# 03_PWR.net
KiCad netlist of a schematic drawn in Altium Designer
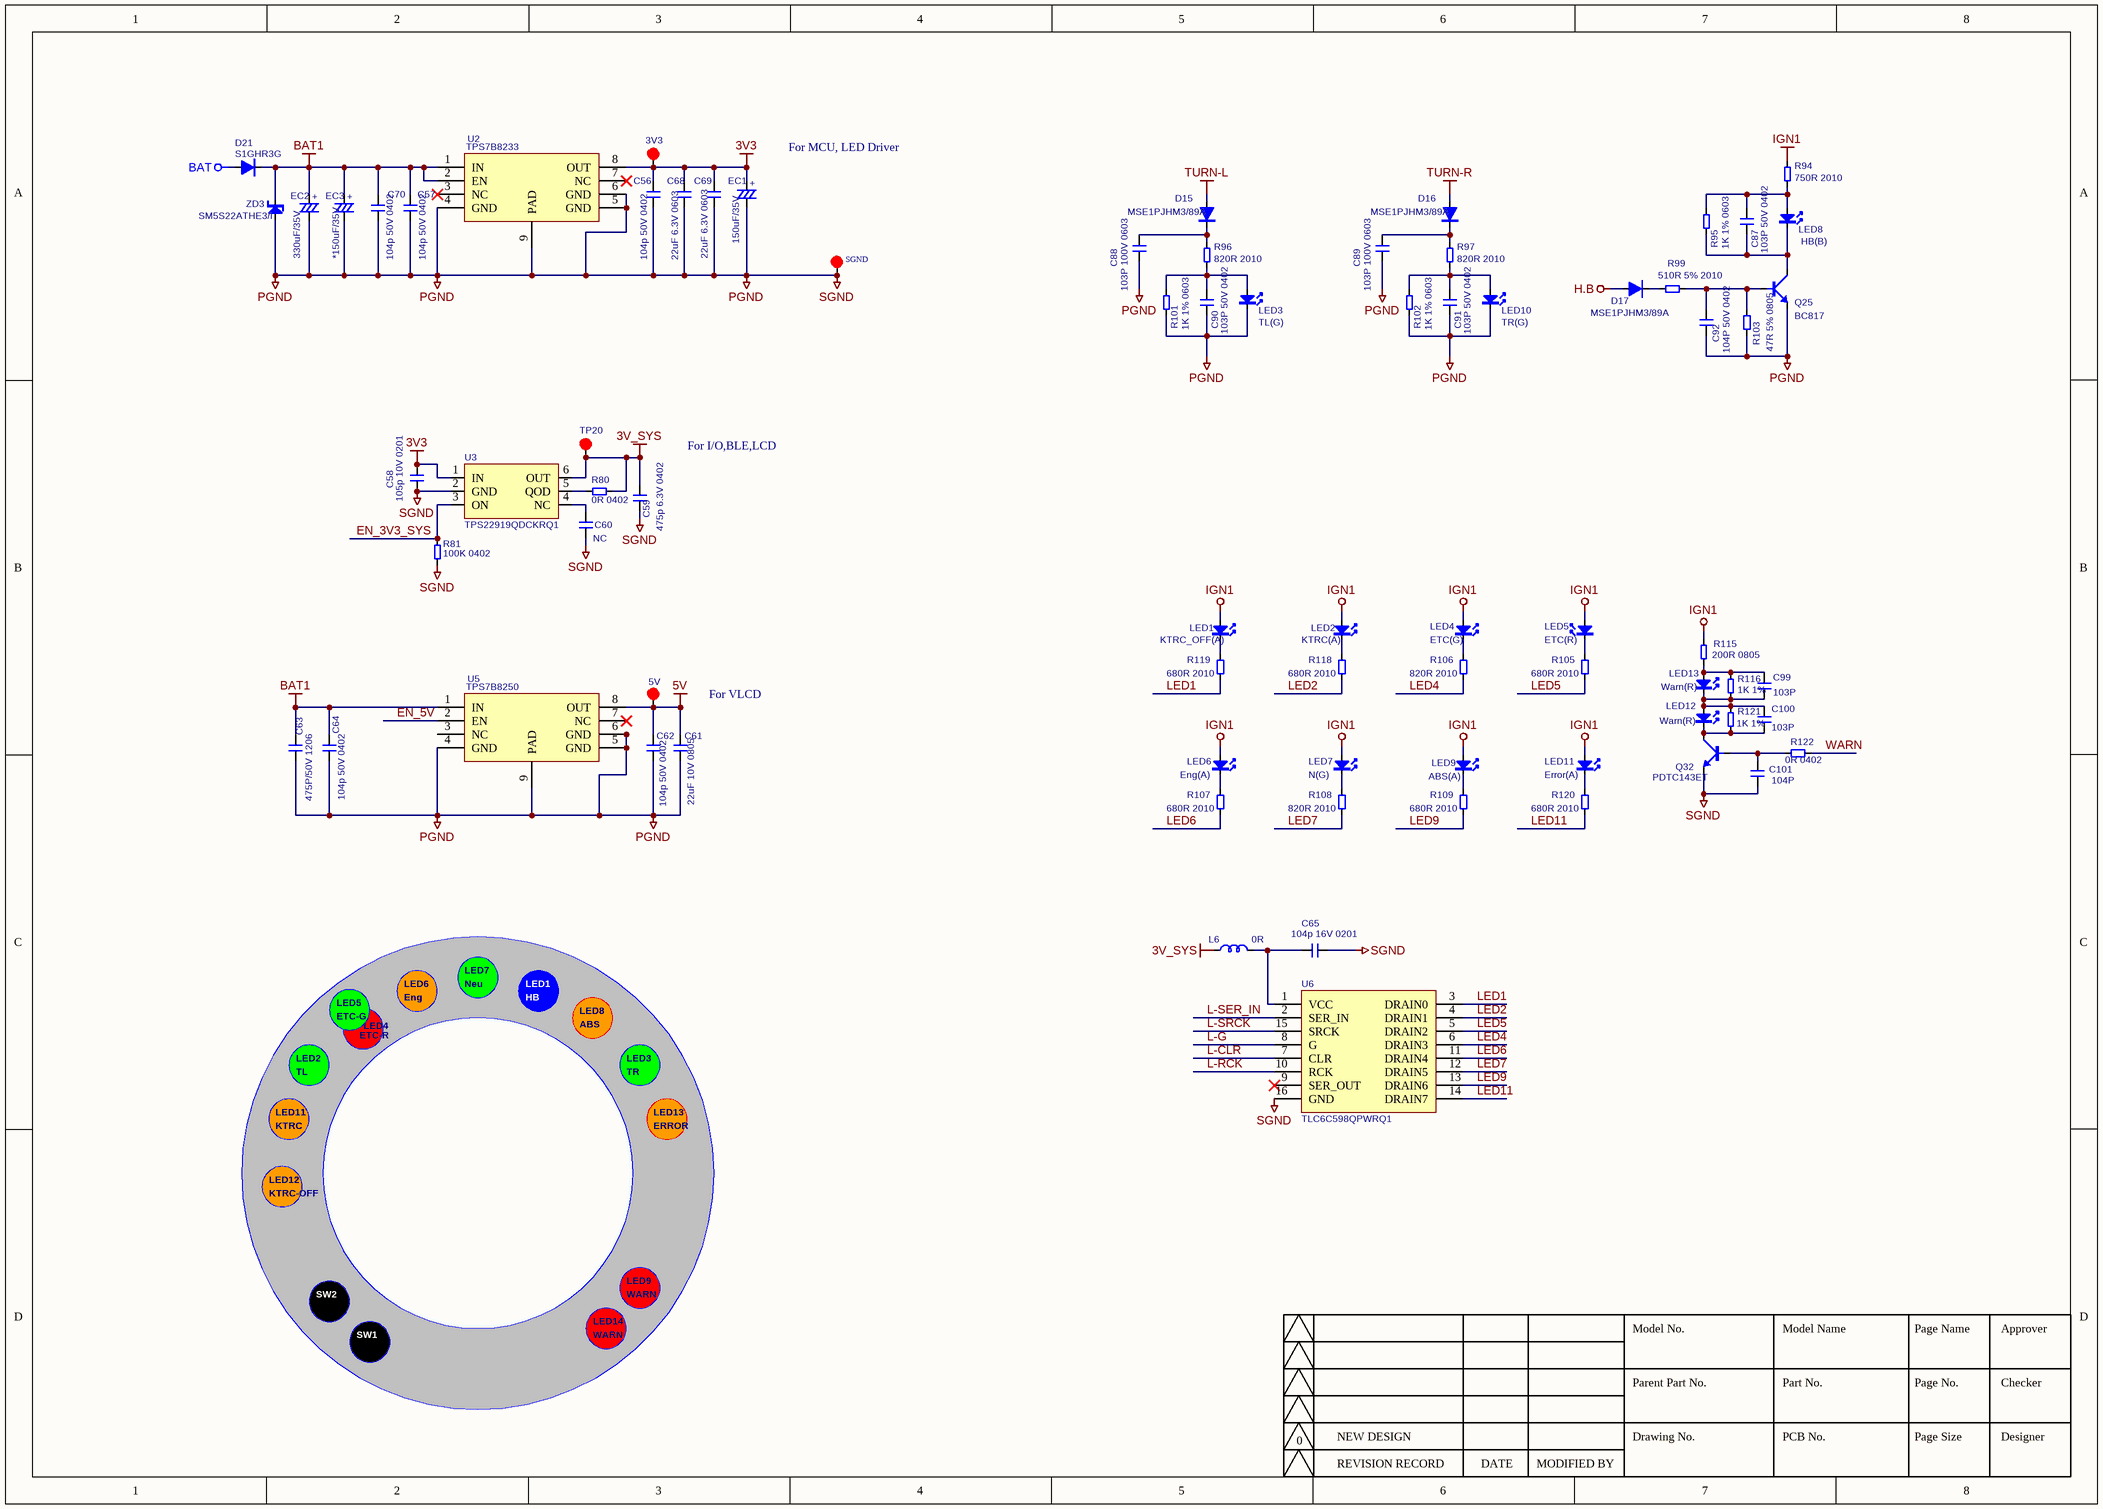
[diagram p0: 03_PWR.SchDoc]

(export (version "E")
  (design (tool "Eeschema 10.0.6"))
  (components
    (comp (ref "3V3") (value "TEST") (footprint "TEST") (libsource (lib "CTE-Lib(Meter)") (part "TEST")))
    (comp (ref "5V") (value "TEST") (footprint "TEST") (libsource (lib "CTE-Lib(Meter)") (part "TEST")))
    (comp (ref "C56")
      (value "104p 50V 0402")
      (footprint "C0402")
      (description "Capacitor")
      (libsource (lib "*") (part "C"))
    )
    (comp (ref "C57")
      (value "104p 50V 0402")
      (footprint "C0402")
      (description "Capacitor")
      (libsource (lib "*") (part "C"))
    )
    (comp (ref "C58")
      (value "105p 10V 0201")
      (footprint "C0201")
      (description "Capacitor")
      (libsource (lib "*") (part "C"))
    )
    (comp (ref "C59")
      (value "475p 6.3V 0402")
      (footprint "C0402")
      (description "4.7uF 6.3V 0402")
      (fields (field (name "VOLTAGE") "6.3V"))
      (libsource (lib "CTE") (part "C"))
    )
    (comp (ref "C60")
      (value "NC")
      (footprint "C0402")
      (description "Capacitor")
      (libsource (lib "CTE") (part "C"))
    )
    (comp (ref "C61")
      (value "22uF 10V 0805")
      (footprint "C0805")
      (description "Capacitor")
      (libsource (lib "CTE") (part "C"))
    )
    (comp (ref "C62")
      (value "104p 50V 0402")
      (footprint "C0402")
      (description "Capacitor")
      (libsource (lib "*") (part "C"))
    )
    (comp (ref "C63")
      (value "475P/50V 1206")
      (footprint "C1206")
      (description "Capacitor")
      (libsource (lib "CTE") (part "C"))
    )
    (comp (ref "C64")
      (value "104p 50V 0402")
      (footprint "C0402")
      (description "Capacitor")
      (libsource (lib "*") (part "C"))
    )
    (comp (ref "C65")
      (value "104p 16V 0201")
      (footprint "C0201")
      (description "Capacitor")
      (libsource (lib "*") (part "C"))
    )
    (comp (ref "C68")
      (value "22uF 6.3V 0603")
      (footprint "C0603")
      (description "Capacitor")
      (libsource (lib "CTE") (part "C"))
    )
    (comp (ref "C69")
      (value "22uF 6.3V 0603")
      (footprint "C0603")
      (description "Capacitor")
      (libsource (lib "CTE") (part "C"))
    )
    (comp (ref "C70")
      (value "104p 50V 0402")
      (footprint "C0402")
      (description "Capacitor")
      (libsource (lib "*") (part "C"))
    )
    (comp (ref "C87")
      (value "103P 50V 0402")
      (footprint "C0402")
      (description "Capacitor")
      (libsource (lib "CTE") (part "C"))
    )
    (comp (ref "C88")
      (value "103P 100V 0603")
      (footprint "C0603")
      (description "Capacitor")
      (libsource (lib "CTE") (part "C"))
    )
    (comp (ref "C89")
      (value "103P 100V 0603")
      (footprint "C0603")
      (description "Capacitor")
      (libsource (lib "CTE") (part "C"))
    )
    (comp (ref "C90")
      (value "103P 50V 0402")
      (footprint "C0402")
      (description "Capacitor")
      (libsource (lib "CTE") (part "C"))
    )
    (comp (ref "C91")
      (value "103P 50V 0402")
      (footprint "C0402")
      (description "Capacitor")
      (libsource (lib "CTE") (part "C"))
    )
    (comp (ref "C92")
      (value "104P 50V 0402")
      (footprint "C0402")
      (description "Capacitor")
      (libsource (lib "CTE") (part "C"))
    )
    (comp (ref "C99")
      (value "103P")
      (footprint "C0402")
      (description "Capacitor")
      (libsource (lib "CTE") (part "C"))
    )
    (comp (ref "C100")
      (value "103P")
      (footprint "C0402")
      (description "Capacitor")
      (libsource (lib "CTE") (part "C"))
    )
    (comp (ref "C101")
      (value "104P")
      (footprint "C0402")
      (description "Capacitor")
      (libsource (lib "CTE") (part "C"))
    )
    (comp (ref "D15")
      (value "MSE1PJHM3/89A")
      (footprint "D-DO-219AD")
      (description "SK54-AU/BAS16/RR264/1N4148/FM4004/SS14/SSL14/V15PL50/DO-219AD")
      (libsource (lib "") (part "D-SMD_1"))
    )
    (comp (ref "D16")
      (value "MSE1PJHM3/89A")
      (footprint "D-DO-219AD")
      (description "SK54-AU/BAS16/RR264/1N4148/FM4004/SS14/SSL14/V15PL50/DO-219AD")
      (libsource (lib "") (part "D-SMD_1"))
    )
    (comp (ref "D17")
      (value "MSE1PJHM3/89A")
      (footprint "D-DO-219AD")
      (description "SK54-AU/BAS16/RR264/1N4148/FM4004/SS14/SSL14/V15PL50/DO-219AD")
      (libsource (lib "CTE") (part "D-SMD"))
    )
    (comp (ref "D21")
      (value "S1GHR3G")
      (footprint "D-SMA")
      (description "BAS16/RR264/1N4148/FM4004/SS14/SSL14/V15PL50")
      (libsource (lib "CTE") (part "D-SMD"))
    )
    (comp (ref "EC1")
      (value "150uF/35V")
      (footprint "EC-[6.8*8]")
      (description "電解電容")
      (libsource (lib "CTE") (part "C-EC"))
    )
    (comp (ref "EC2")
      (value "330uF/35V")
      (footprint "EC-[8.5*10]")
      (description "電解電容")
      (libsource (lib "CTE") (part "C-EC"))
    )
    (comp (ref "EC3")
      (value "*150uF/35V")
      (footprint "EC-[6.8*8]")
      (description "電解電容")
      (libsource (lib "CTE") (part "C-EC"))
    )
    (comp (ref "L6")
      (value "0R")
      (footprint "0603")
      (description "BEAD101")
      (libsource (lib "CTE") (part "L"))
    )
    (comp (ref "LED1") (value "KTRC_OFF(A)") (footprint "LED-1206") (libsource (lib "CTE") (part "LED")))
    (comp (ref "LED2") (value "KTRC(A)") (footprint "LED-1206") (libsource (lib "CTE") (part "LED")))
    (comp (ref "LED3") (value "TL(G)") (footprint "LED-1206") (libsource (lib "CTE") (part "LED")))
    (comp (ref "LED4") (value "ETC(G)") (footprint "LED-1206") (libsource (lib "CTE") (part "LED")))
    (comp (ref "LED5") (value "ETC(R)") (footprint "LED-1206") (libsource (lib "") (part "LED_1")))
    (comp (ref "LED6") (value "Eng(A)") (footprint "LED-1206") (libsource (lib "CTE") (part "LED")))
    (comp (ref "LED7") (value "N(G)") (footprint "LED-1206") (libsource (lib "CTE") (part "LED")))
    (comp (ref "LED8") (value "HB(B)") (footprint "LED-1206") (libsource (lib "CTE") (part "LED")))
    (comp (ref "LED9") (value "ABS(A)") (footprint "LED-1206") (libsource (lib "CTE") (part "LED")))
    (comp (ref "LED10") (value "TR(G)") (footprint "LED-1206") (libsource (lib "CTE") (part "LED")))
    (comp (ref "LED11") (value "Error(A)") (footprint "LED-1206") (libsource (lib "CTE") (part "LED")))
    (comp (ref "LED12") (value "Warn(R)") (footprint "LED-1206") (libsource (lib "CTE") (part "LED")))
    (comp (ref "LED13") (value "Warn(R)") (footprint "LED-1206") (libsource (lib "CTE") (part "LED")))
    (comp (ref "Q25")
      (value "BC817")
      (footprint "SOT23-RF")
      (description "BC817，PDTC143ET，2SD2211，2SD1918")
      (libsource (lib "") (part "Q-NPN(BCE)_1"))
    )
    (comp (ref "Q32")
      (value "PDTC143ET")
      (footprint "SOT23-RF")
      (description "BC817/PDTC143ET/2SD2211/2SD1918")
      (libsource (lib "CTE") (part "Q-NPN(BCE)"))
    )
    (comp (ref "R80")
      (value "0R 0402")
      (footprint "0402")
      (description "0603")
      (libsource (lib "CTE") (part "R-0603"))
    )
    (comp (ref "R81") (value "100K 0402") (footprint "0402") (libsource (lib "*") (part "R")))
    (comp (ref "R94") (value "750R 2010") (footprint "2010") (libsource (lib "*") (part "R")))
    (comp (ref "R95") (value "1K 1% 0603") (footprint "0603") (libsource (lib "*") (part "R")))
    (comp (ref "R96") (value "820R 2010") (footprint "2010") (libsource (lib "*") (part "R")))
    (comp (ref "R97") (value "820R 2010") (footprint "2010") (libsource (lib "*") (part "R")))
    (comp (ref "R99") (value "510R 5% 2010") (footprint "2010") (libsource (lib "CTE") (part "R")))
    (comp (ref "R101") (value "1K 1% 0603") (footprint "0603") (libsource (lib "*") (part "R")))
    (comp (ref "R102") (value "1K 1% 0603") (footprint "0603") (libsource (lib "*") (part "R")))
    (comp (ref "R103") (value "47R 5% 0805") (footprint "0805") (libsource (lib "CTE") (part "R")))
    (comp (ref "R105")
      (value "680R 2010")
      (footprint "2010")
      (description "2010")
      (libsource (lib "CTE") (part "R-2010"))
    )
    (comp (ref "R106")
      (value "820R 2010")
      (footprint "2010")
      (description "2010")
      (libsource (lib "CTE") (part "R-2010"))
    )
    (comp (ref "R107")
      (value "680R 2010")
      (footprint "2010")
      (description "2010")
      (libsource (lib "CTE") (part "R-2010"))
    )
    (comp (ref "R108")
      (value "820R 2010")
      (footprint "2010")
      (description "2010")
      (libsource (lib "CTE") (part "R-2010"))
    )
    (comp (ref "R109")
      (value "680R 2010")
      (footprint "2010")
      (description "2010")
      (libsource (lib "CTE") (part "R-2010"))
    )
    (comp (ref "R115") (value "200R 0805") (footprint "0805") (libsource (lib "*") (part "R")))
    (comp (ref "R116") (value "1K 1%") (footprint "0603") (libsource (lib "*") (part "R")))
    (comp (ref "R118")
      (value "680R 2010")
      (footprint "2010")
      (description "2010")
      (libsource (lib "CTE") (part "R-2010"))
    )
    (comp (ref "R119")
      (value "680R 2010")
      (footprint "2010")
      (description "2010")
      (libsource (lib "CTE") (part "R-2010"))
    )
    (comp (ref "R120")
      (value "680R 2010")
      (footprint "2010")
      (description "2010")
      (libsource (lib "CTE") (part "R-2010"))
    )
    (comp (ref "R121") (value "1K 1%") (footprint "0603") (libsource (lib "*") (part "R")))
    (comp (ref "R122") (value "0R 0402") (footprint "0402") (libsource (lib "CTE") (part "R")))
    (comp (ref "SGND") (value "TEST") (footprint "TEST") (libsource (lib "CTE") (part "TEST")))
    (comp (ref "TP20") (value "TEST") (footprint "TEST") (libsource (lib "CTE") (part "TEST")))
    (comp (ref "U2")
      (value "TPS7B8233")
      (footprint "IC-MSOP8(3*3mm)")
      (libsource (lib "CTE") (part "IC-TPS7B82-Q1"))
    )
    (comp (ref "U3")
      (value "TPS22919QDCKRQ1")
      (footprint "IC-R-PDSO-G6")
      (libsource (lib "Schlib1") (part "TPS22919QDCKRQ1"))
    )
    (comp (ref "U5")
      (value "TPS7B8250")
      (footprint "IC-MSOP8(3*3mm)")
      (libsource (lib "CTE") (part "IC-TPS7B82-Q1"))
    )
    (comp (ref "U6")
      (value "TLC6C598QPWRQ1")
      (footprint "IC-TSSOP16")
      (libsource (lib "TFT_Test Card-00") (part "IC-TLC6C598"))
    )
    (comp (ref "ZD3") (value "SM5S22ATHE3/I") (footprint "ZD-DO218AB") (libsource (lib "CTE") (part "ZENER")))
  )
  (nets
    (net (code "1") (name "/EN_3V3_SYS") (class "Default")
      (node (ref "R81") (pin "1") (pinfunction "1_1") (pintype "passive"))
      (node (ref "U3") (pin "3") (pinfunction "ON_3") (pintype "passive"))
    )
    (net (code "2") (name "/EN_5V") (class "Default")
      (node (ref "U5") (pin "2") (pinfunction "EN_2") (pintype "passive"))
    )
    (net (code "3") (name "/L-CLR") (class "Default")
      (node (ref "U6") (pin "7") (pinfunction "CLR_7") (pintype "passive"))
    )
    (net (code "4") (name "/L-G") (class "Default")
      (node (ref "U6") (pin "8") (pinfunction "G_8") (pintype "passive"))
    )
    (net (code "5") (name "/L-RCK") (class "Default")
      (node (ref "U6") (pin "10") (pinfunction "RCK_10") (pintype "passive"))
    )
    (net (code "6") (name "/L-SER_IN") (class "Default")
      (node (ref "U6") (pin "2") (pinfunction "SER_IN_2") (pintype "passive"))
    )
    (net (code "7") (name "/L-SRCK") (class "Default")
      (node (ref "U6") (pin "15") (pinfunction "SRCK_15") (pintype "passive"))
    )
    (net (code "8") (name "/LED1") (class "Default")
      (node (ref "R119") (pin "1") (pinfunction "1_1") (pintype "passive"))
      (node (ref "U6") (pin "3") (pinfunction "DRAIN0_3") (pintype "passive"))
    )
    (net (code "9") (name "/LED2") (class "Default")
      (node (ref "R118") (pin "1") (pinfunction "1_1") (pintype "passive"))
      (node (ref "U6") (pin "4") (pinfunction "DRAIN1_4") (pintype "passive"))
    )
    (net (code "10") (name "/LED4") (class "Default")
      (node (ref "R106") (pin "1") (pinfunction "1_1") (pintype "passive"))
      (node (ref "U6") (pin "6") (pinfunction "DRAIN3_6") (pintype "passive"))
    )
    (net (code "11") (name "/LED5") (class "Default")
      (node (ref "R105") (pin "1") (pinfunction "1_1") (pintype "passive"))
      (node (ref "U6") (pin "5") (pinfunction "DRAIN2_5") (pintype "passive"))
    )
    (net (code "12") (name "/LED6") (class "Default")
      (node (ref "R107") (pin "1") (pinfunction "1_1") (pintype "passive"))
      (node (ref "U6") (pin "11") (pinfunction "DRAIN4_11") (pintype "passive"))
    )
    (net (code "13") (name "/LED7") (class "Default")
      (node (ref "R108") (pin "1") (pinfunction "1_1") (pintype "passive"))
      (node (ref "U6") (pin "12") (pinfunction "DRAIN5_12") (pintype "passive"))
    )
    (net (code "14") (name "/LED9") (class "Default")
      (node (ref "R109") (pin "1") (pinfunction "1_1") (pintype "passive"))
      (node (ref "U6") (pin "13") (pinfunction "DRAIN6_13") (pintype "passive"))
    )
    (net (code "15") (name "/LED11") (class "Default")
      (node (ref "R120") (pin "1") (pinfunction "1_1") (pintype "passive"))
      (node (ref "U6") (pin "14") (pinfunction "DRAIN7_14") (pintype "passive"))
    )
    (net (code "16") (name "/WARN") (class "Default")
      (node (ref "R122") (pin "1") (pinfunction "1_1") (pintype "passive"))
    )
    (net (code "17") (name "3V3") (class "Default")
      (node (ref "3V3") (pin "TP") (pinfunction "TP_TP") (pintype "passive"))
      (node (ref "C56") (pin "1") (pinfunction "1_1") (pintype "passive"))
      (node (ref "C58") (pin "2") (pinfunction "2_2") (pintype "passive"))
      (node (ref "C68") (pin "1") (pinfunction "1_1") (pintype "passive"))
      (node (ref "C69") (pin "1") (pinfunction "1_1") (pintype "passive"))
      (node (ref "EC1") (pin "1") (pinfunction "1_1") (pintype "passive"))
      (node (ref "U2") (pin "8") (pinfunction "OUT_8") (pintype "passive"))
      (node (ref "U3") (pin "1") (pinfunction "IN_1") (pintype "passive"))
    )
    (net (code "18") (name "3V_SYS") (class "Default")
      (node (ref "C59") (pin "1") (pinfunction "1_1") (pintype "passive"))
      (node (ref "L6") (pin "1") (pinfunction "1_1") (pintype "passive"))
      (node (ref "R80") (pin "2") (pinfunction "2_2") (pintype "passive"))
      (node (ref "TP20") (pin "TP") (pinfunction "TP_TP") (pintype "passive"))
      (node (ref "U3") (pin "6") (pinfunction "OUT_6") (pintype "passive"))
    )
    (net (code "19") (name "5V") (class "Default")
      (node (ref "5V") (pin "TP") (pinfunction "TP_TP") (pintype "passive"))
      (node (ref "C61") (pin "1") (pinfunction "1_1") (pintype "passive"))
      (node (ref "C62") (pin "1") (pinfunction "1_1") (pintype "passive"))
      (node (ref "U5") (pin "8") (pinfunction "OUT_8") (pintype "passive"))
    )
    (net (code "20") (name "BAT") (class "Default")
      (node (ref "D21") (pin "1") (pinfunction "A_1") (pintype "passive"))
    )
    (net (code "21") (name "BAT1") (class "Default")
      (node (ref "C57") (pin "1") (pinfunction "1_1") (pintype "passive"))
      (node (ref "C63") (pin "1") (pinfunction "1_1") (pintype "passive"))
      (node (ref "C64") (pin "1") (pinfunction "1_1") (pintype "passive"))
      (node (ref "C70") (pin "1") (pinfunction "1_1") (pintype "passive"))
      (node (ref "D21") (pin "2") (pinfunction "K_2") (pintype "passive"))
      (node (ref "EC2") (pin "1") (pinfunction "1_1") (pintype "passive"))
      (node (ref "EC3") (pin "1") (pinfunction "1_1") (pintype "passive"))
      (node (ref "U2") (pin "1") (pinfunction "IN_1") (pintype "passive"))
      (node (ref "U2") (pin "2") (pinfunction "EN_2") (pintype "passive"))
      (node (ref "U5") (pin "1") (pinfunction "IN_1") (pintype "passive"))
      (node (ref "ZD3") (pin "2") (pinfunction "K_2") (pintype "passive"))
    )
    (net (code "22") (name "H.B") (class "Default")
      (node (ref "D17") (pin "1") (pinfunction "A_1") (pintype "passive"))
    )
    (net (code "23") (name "IGN1") (class "Default")
      (node (ref "LED1") (pin "A") (pinfunction "A_A") (pintype "passive"))
      (node (ref "LED11") (pin "A") (pinfunction "A_A") (pintype "passive"))
      (node (ref "LED2") (pin "A") (pinfunction "A_A") (pintype "passive"))
      (node (ref "LED4") (pin "A") (pinfunction "A_A") (pintype "passive"))
      (node (ref "LED5") (pin "A") (pinfunction "A_A") (pintype "passive"))
      (node (ref "LED6") (pin "A") (pinfunction "A_A") (pintype "passive"))
      (node (ref "LED7") (pin "A") (pinfunction "A_A") (pintype "passive"))
      (node (ref "LED9") (pin "A") (pinfunction "A_A") (pintype "passive"))
      (node (ref "R115") (pin "2") (pinfunction "2_2") (pintype "passive"))
      (node (ref "R94") (pin "1") (pinfunction "1_1") (pintype "passive"))
    )
    (net (code "24") (name "Net-(C87-Pad1)") (class "Default")
      (node (ref "C87") (pin "1") (pinfunction "1_1") (pintype "passive"))
      (node (ref "LED8") (pin "A") (pinfunction "A_A") (pintype "passive"))
      (node (ref "R94") (pin "2") (pinfunction "2_2") (pintype "passive"))
      (node (ref "R95") (pin "1") (pinfunction "1_1") (pintype "passive"))
    )
    (net (code "25") (name "Net-(C90-Pad1)") (class "Default")
      (node (ref "C90") (pin "1") (pinfunction "1_1") (pintype "passive"))
      (node (ref "LED3") (pin "A") (pinfunction "A_A") (pintype "passive"))
      (node (ref "R101") (pin "1") (pinfunction "1_1") (pintype "passive"))
      (node (ref "R96") (pin "2") (pinfunction "2_2") (pintype "passive"))
    )
    (net (code "26") (name "Net-(C91-Pad1)") (class "Default")
      (node (ref "C91") (pin "1") (pinfunction "1_1") (pintype "passive"))
      (node (ref "LED10") (pin "A") (pinfunction "A_A") (pintype "passive"))
      (node (ref "R102") (pin "1") (pinfunction "1_1") (pintype "passive"))
      (node (ref "R97") (pin "2") (pinfunction "2_2") (pintype "passive"))
    )
    (net (code "27") (name "Net-(C99-Pad1)") (class "Default")
      (node (ref "C99") (pin "1") (pinfunction "1_1") (pintype "passive"))
      (node (ref "LED13") (pin "A") (pinfunction "A_A") (pintype "passive"))
      (node (ref "R115") (pin "1") (pinfunction "1_1") (pintype "passive"))
      (node (ref "R116") (pin "1") (pinfunction "1_1") (pintype "passive"))
    )
    (net (code "28") (name "Net-(C100-Pad1)") (class "Default")
      (node (ref "C100") (pin "1") (pinfunction "1_1") (pintype "passive"))
      (node (ref "C99") (pin "2") (pinfunction "2_2") (pintype "passive"))
      (node (ref "LED12") (pin "A") (pinfunction "A_A") (pintype "passive"))
      (node (ref "LED13") (pin "K") (pinfunction "K_K") (pintype "passive"))
      (node (ref "R116") (pin "2") (pinfunction "2_2") (pintype "passive"))
      (node (ref "R121") (pin "1") (pinfunction "1_1") (pintype "passive"))
    )
    (net (code "29") (name "Net-(D15-K)") (class "Default")
      (node (ref "C88") (pin "1") (pinfunction "1_1") (pintype "passive"))
      (node (ref "D15") (pin "2") (pinfunction "K_2") (pintype "passive"))
      (node (ref "R96") (pin "1") (pinfunction "1_1") (pintype "passive"))
    )
    (net (code "30") (name "Net-(D16-K)") (class "Default")
      (node (ref "C89") (pin "1") (pinfunction "1_1") (pintype "passive"))
      (node (ref "D16") (pin "2") (pinfunction "K_2") (pintype "passive"))
      (node (ref "R97") (pin "1") (pinfunction "1_1") (pintype "passive"))
    )
    (net (code "31") (name "Net-(D17-K)") (class "Default")
      (node (ref "D17") (pin "2") (pinfunction "K_2") (pintype "passive"))
      (node (ref "R99") (pin "1") (pinfunction "1_1") (pintype "passive"))
    )
    (net (code "32") (name "Net-(LED1-PadK)") (class "Default")
      (node (ref "LED1") (pin "K") (pinfunction "K_K") (pintype "passive"))
      (node (ref "R119") (pin "2") (pinfunction "2_2") (pintype "passive"))
    )
    (net (code "33") (name "Net-(LED2-PadK)") (class "Default")
      (node (ref "LED2") (pin "K") (pinfunction "K_K") (pintype "passive"))
      (node (ref "R118") (pin "2") (pinfunction "2_2") (pintype "passive"))
    )
    (net (code "34") (name "Net-(LED4-PadK)") (class "Default")
      (node (ref "LED4") (pin "K") (pinfunction "K_K") (pintype "passive"))
      (node (ref "R106") (pin "2") (pinfunction "2_2") (pintype "passive"))
    )
    (net (code "35") (name "Net-(LED5-PadK)") (class "Default")
      (node (ref "LED5") (pin "K") (pinfunction "K_K") (pintype "passive"))
      (node (ref "R105") (pin "2") (pinfunction "2_2") (pintype "passive"))
    )
    (net (code "36") (name "Net-(LED6-PadK)") (class "Default")
      (node (ref "LED6") (pin "K") (pinfunction "K_K") (pintype "passive"))
      (node (ref "R107") (pin "2") (pinfunction "2_2") (pintype "passive"))
    )
    (net (code "37") (name "Net-(LED7-PadK)") (class "Default")
      (node (ref "LED7") (pin "K") (pinfunction "K_K") (pintype "passive"))
      (node (ref "R108") (pin "2") (pinfunction "2_2") (pintype "passive"))
    )
    (net (code "38") (name "Net-(LED9-PadK)") (class "Default")
      (node (ref "LED9") (pin "K") (pinfunction "K_K") (pintype "passive"))
      (node (ref "R109") (pin "2") (pinfunction "2_2") (pintype "passive"))
    )
    (net (code "39") (name "Net-(LED11-PadK)") (class "Default")
      (node (ref "LED11") (pin "K") (pinfunction "K_K") (pintype "passive"))
      (node (ref "R120") (pin "2") (pinfunction "2_2") (pintype "passive"))
    )
    (net (code "40") (name "Net-(Q25-B)") (class "Default")
      (node (ref "C92") (pin "1") (pinfunction "1_1") (pintype "passive"))
      (node (ref "Q25") (pin "1") (pinfunction "B_1") (pintype "passive"))
      (node (ref "R103") (pin "1") (pinfunction "1_1") (pintype "passive"))
      (node (ref "R99") (pin "2") (pinfunction "2_2") (pintype "passive"))
    )
    (net (code "41") (name "Net-(Q25-C)") (class "Default")
      (node (ref "C87") (pin "2") (pinfunction "2_2") (pintype "passive"))
      (node (ref "LED8") (pin "K") (pinfunction "K_K") (pintype "passive"))
      (node (ref "Q25") (pin "2") (pinfunction "C_2") (pintype "passive"))
      (node (ref "R95") (pin "2") (pinfunction "2_2") (pintype "passive"))
    )
    (net (code "42") (name "Net-(Q32-B)") (class "Default")
      (node (ref "C101") (pin "1") (pinfunction "1_1") (pintype "passive"))
      (node (ref "Q32") (pin "1") (pinfunction "B_1") (pintype "passive"))
      (node (ref "R122") (pin "2") (pinfunction "2_2") (pintype "passive"))
    )
    (net (code "43") (name "Net-(Q32-C)") (class "Default")
      (node (ref "C100") (pin "2") (pinfunction "2_2") (pintype "passive"))
      (node (ref "LED12") (pin "K") (pinfunction "K_K") (pintype "passive"))
      (node (ref "Q32") (pin "2") (pinfunction "C_2") (pintype "passive"))
      (node (ref "R121") (pin "2") (pinfunction "2_2") (pintype "passive"))
    )
    (net (code "44") (name "Net-(U3-NC)") (class "Default")
      (node (ref "C60") (pin "2") (pinfunction "2_2") (pintype "passive"))
      (node (ref "U3") (pin "4") (pinfunction "NC_4") (pintype "passive"))
    )
    (net (code "45") (name "Net-(U3-QOD)") (class "Default")
      (node (ref "R80") (pin "1") (pinfunction "1_1") (pintype "passive"))
      (node (ref "U3") (pin "5") (pinfunction "QOD_5") (pintype "passive"))
    )
    (net (code "46") (name "Net-(U6-VCC)") (class "Default")
      (node (ref "C65") (pin "1") (pinfunction "1_1") (pintype "passive"))
      (node (ref "L6") (pin "2") (pinfunction "2_2") (pintype "passive"))
      (node (ref "U6") (pin "1") (pinfunction "VCC_1") (pintype "passive"))
    )
    (net (code "47") (name "PGND") (class "Default")
      (node (ref "C101") (pin "2") (pinfunction "2_2") (pintype "passive"))
      (node (ref "C56") (pin "2") (pinfunction "2_2") (pintype "passive"))
      (node (ref "C57") (pin "2") (pinfunction "2_2") (pintype "passive"))
      (node (ref "C58") (pin "1") (pinfunction "1_1") (pintype "passive"))
      (node (ref "C59") (pin "2") (pinfunction "2_2") (pintype "passive"))
      (node (ref "C60") (pin "1") (pinfunction "1_1") (pintype "passive"))
      (node (ref "C61") (pin "2") (pinfunction "2_2") (pintype "passive"))
      (node (ref "C62") (pin "2") (pinfunction "2_2") (pintype "passive"))
      (node (ref "C63") (pin "2") (pinfunction "2_2") (pintype "passive"))
      (node (ref "C64") (pin "2") (pinfunction "2_2") (pintype "passive"))
      (node (ref "C65") (pin "2") (pinfunction "2_2") (pintype "passive"))
      (node (ref "C68") (pin "2") (pinfunction "2_2") (pintype "passive"))
      (node (ref "C69") (pin "2") (pinfunction "2_2") (pintype "passive"))
      (node (ref "C70") (pin "2") (pinfunction "2_2") (pintype "passive"))
      (node (ref "C88") (pin "2") (pinfunction "2_2") (pintype "passive"))
      (node (ref "C89") (pin "2") (pinfunction "2_2") (pintype "passive"))
      (node (ref "C90") (pin "2") (pinfunction "2_2") (pintype "passive"))
      (node (ref "C91") (pin "2") (pinfunction "2_2") (pintype "passive"))
      (node (ref "C92") (pin "2") (pinfunction "2_2") (pintype "passive"))
      (node (ref "EC1") (pin "2") (pinfunction "2_2") (pintype "passive"))
      (node (ref "EC2") (pin "2") (pinfunction "2_2") (pintype "passive"))
      (node (ref "EC3") (pin "2") (pinfunction "2_2") (pintype "passive"))
      (node (ref "LED10") (pin "K") (pinfunction "K_K") (pintype "passive"))
      (node (ref "LED3") (pin "K") (pinfunction "K_K") (pintype "passive"))
      (node (ref "Q25") (pin "3") (pinfunction "E_3") (pintype "passive"))
      (node (ref "Q32") (pin "3") (pinfunction "E_3") (pintype "passive"))
      (node (ref "R101") (pin "2") (pinfunction "2_2") (pintype "passive"))
      (node (ref "R102") (pin "2") (pinfunction "2_2") (pintype "passive"))
      (node (ref "R103") (pin "2") (pinfunction "2_2") (pintype "passive"))
      (node (ref "R81") (pin "2") (pinfunction "2_2") (pintype "passive"))
      (node (ref "SGND") (pin "TP") (pinfunction "TP_TP") (pintype "passive"))
      (node (ref "U2") (pin "4") (pinfunction "GND_4") (pintype "passive"))
      (node (ref "U2") (pin "5") (pinfunction "GND_5") (pintype "passive"))
      (node (ref "U2") (pin "6") (pinfunction "GND_6") (pintype "passive"))
      (node (ref "U2") (pin "9") (pinfunction "PAD_9") (pintype "passive"))
      (node (ref "U3") (pin "2") (pinfunction "GND_2") (pintype "passive"))
      (node (ref "U5") (pin "4") (pinfunction "GND_4") (pintype "passive"))
      (node (ref "U5") (pin "5") (pinfunction "GND_5") (pintype "passive"))
      (node (ref "U5") (pin "6") (pinfunction "GND_6") (pintype "passive"))
      (node (ref "U5") (pin "9") (pinfunction "PAD_9") (pintype "passive"))
      (node (ref "U6") (pin "16") (pinfunction "GND_16") (pintype "passive"))
      (node (ref "ZD3") (pin "1") (pinfunction "A_1") (pintype "passive"))
    )
    (net (code "48") (name "TURN-L") (class "Default")
      (node (ref "D15") (pin "1") (pinfunction "A_1") (pintype "passive"))
    )
    (net (code "49") (name "TURN-R") (class "Default")
      (node (ref "D16") (pin "1") (pinfunction "A_1") (pintype "passive"))
    )
    (net (code "50") (name "unconnected-(U2-NC-Pad3)") (class "Default")
      (node (ref "U2") (pin "3") (pinfunction "NC_3") (pintype "passive+no_connect"))
    )
    (net (code "51") (name "unconnected-(U2-NC-Pad7)") (class "Default")
      (node (ref "U2") (pin "7") (pinfunction "NC_7") (pintype "passive+no_connect"))
    )
    (net (code "52") (name "unconnected-(U5-NC-Pad3)") (class "Default")
      (node (ref "U5") (pin "3") (pinfunction "NC_3") (pintype "passive"))
    )
    (net (code "53") (name "unconnected-(U5-NC-Pad7)") (class "Default")
      (node (ref "U5") (pin "7") (pinfunction "NC_7") (pintype "passive+no_connect"))
    )
    (net (code "54") (name "unconnected-(U6-SER_OUT-Pad9)") (class "Default")
      (node (ref "U6") (pin "9") (pinfunction "SER_OUT_9") (pintype "passive+no_connect"))
    )
  )
)
